# domus-silicea_-_N1_-_nRF24L01.net
KiCad netlist of a schematic drawn in EAGLE
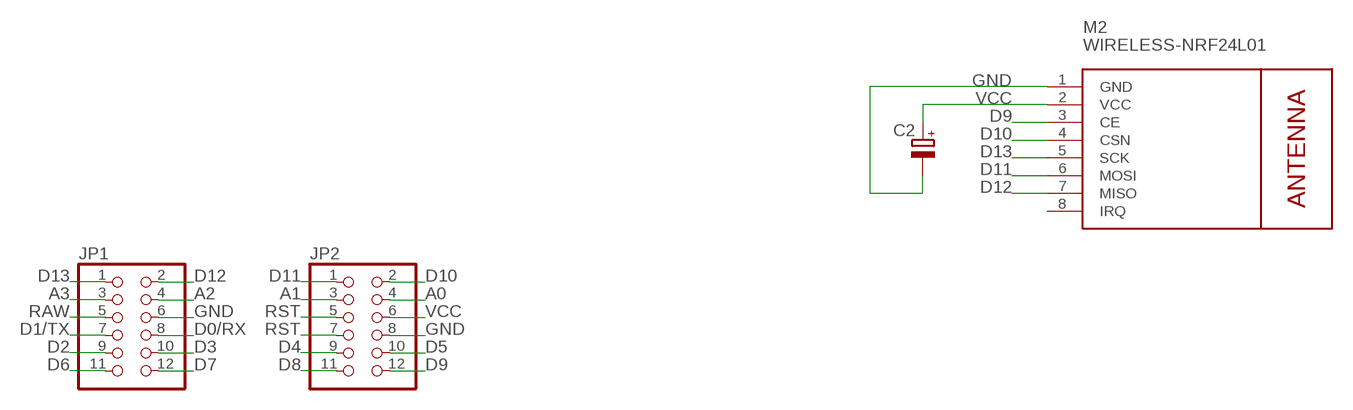
[diagram p0: schematic, sheet 1]

(export (version "E")
  (design (tool "Eeschema 10.0.6"))
  (components
    (comp (ref "C2")
      (value "CPOL-EUE2,5-6E")
      (footprint "eagle-import:E2,5-6E")
      (libsource (lib "eagle-import") (part "CPOL-EUE2,5-6E"))
    )
    (comp (ref "JP1")
      (value "PINHD-2X6")
      (footprint "eagle-import:2X06")
      (libsource (lib "eagle-import") (part "PINHD-2X6"))
    )
    (comp (ref "JP2")
      (value "PINHD-2X6")
      (footprint "eagle-import:2X06")
      (libsource (lib "eagle-import") (part "PINHD-2X6"))
    )
    (comp (ref "M2")
      (value "WIRELESS-NRF24L01")
      (footprint "eagle-import:WIRELESS-NRF24L01")
      (libsource (lib "eagle-import") (part "WIRELESS-NRF24L01"))
    )
  )
  (nets
    (net (code "1") (name "/A0") (class "Default")
      (node (ref "JP2") (pin "4") (pinfunction "4_4") (pintype "passive"))
    )
    (net (code "2") (name "/A1") (class "Default")
      (node (ref "JP2") (pin "3") (pinfunction "3_3") (pintype "passive"))
    )
    (net (code "3") (name "/A2") (class "Default")
      (node (ref "JP1") (pin "4") (pinfunction "4_4") (pintype "passive"))
    )
    (net (code "4") (name "/A3") (class "Default")
      (node (ref "JP1") (pin "3") (pinfunction "3_3") (pintype "passive"))
    )
    (net (code "5") (name "/D0{slash}RX") (class "Default")
      (node (ref "JP1") (pin "8") (pinfunction "8_8") (pintype "passive"))
    )
    (net (code "6") (name "/D1{slash}TX") (class "Default")
      (node (ref "JP1") (pin "7") (pinfunction "7_7") (pintype "passive"))
    )
    (net (code "7") (name "/D2") (class "Default")
      (node (ref "JP1") (pin "9") (pinfunction "9_9") (pintype "passive"))
    )
    (net (code "8") (name "/D3") (class "Default")
      (node (ref "JP1") (pin "10") (pinfunction "10_10") (pintype "passive"))
    )
    (net (code "9") (name "/D4") (class "Default")
      (node (ref "JP2") (pin "9") (pinfunction "9_9") (pintype "passive"))
    )
    (net (code "10") (name "/D5") (class "Default")
      (node (ref "JP2") (pin "10") (pinfunction "10_10") (pintype "passive"))
    )
    (net (code "11") (name "/D6") (class "Default")
      (node (ref "JP1") (pin "11") (pinfunction "11_11") (pintype "passive"))
    )
    (net (code "12") (name "/D7") (class "Default")
      (node (ref "JP1") (pin "12") (pinfunction "12_12") (pintype "passive"))
    )
    (net (code "13") (name "/D8") (class "Default")
      (node (ref "JP2") (pin "11") (pinfunction "11_11") (pintype "passive"))
    )
    (net (code "14") (name "/D9") (class "Default")
      (node (ref "JP2") (pin "12") (pinfunction "12_12") (pintype "passive"))
      (node (ref "M2") (pin "3") (pinfunction "CE_3") (pintype "bidirectional"))
    )
    (net (code "15") (name "/D10") (class "Default")
      (node (ref "JP2") (pin "2") (pinfunction "2_2") (pintype "passive"))
      (node (ref "M2") (pin "4") (pinfunction "CSN_4") (pintype "bidirectional"))
    )
    (net (code "16") (name "/D11") (class "Default")
      (node (ref "JP2") (pin "1") (pinfunction "1_1") (pintype "passive"))
      (node (ref "M2") (pin "6") (pinfunction "MOSI_6") (pintype "bidirectional"))
    )
    (net (code "17") (name "/D12") (class "Default")
      (node (ref "JP1") (pin "2") (pinfunction "2_2") (pintype "passive"))
      (node (ref "M2") (pin "7") (pinfunction "MISO_7") (pintype "bidirectional"))
    )
    (net (code "18") (name "/D13") (class "Default")
      (node (ref "JP1") (pin "1") (pinfunction "1_1") (pintype "passive"))
      (node (ref "M2") (pin "5") (pinfunction "SCK_5") (pintype "bidirectional"))
    )
    (net (code "19") (name "/GND") (class "Default")
      (node (ref "C2") (pin "-") (pinfunction "-_-") (pintype "passive"))
      (node (ref "JP1") (pin "6") (pinfunction "6_6") (pintype "passive"))
      (node (ref "JP2") (pin "8") (pinfunction "8_8") (pintype "passive"))
      (node (ref "M2") (pin "1") (pinfunction "GND_1") (pintype "power_in"))
    )
    (net (code "20") (name "/RAW") (class "Default")
      (node (ref "JP1") (pin "5") (pinfunction "5_5") (pintype "passive"))
    )
    (net (code "21") (name "/RST") (class "Default")
      (node (ref "JP2") (pin "5") (pinfunction "5_5") (pintype "passive"))
      (node (ref "JP2") (pin "7") (pinfunction "7_7") (pintype "passive"))
    )
    (net (code "22") (name "/VCC") (class "Default")
      (node (ref "C2") (pin "+") (pinfunction "+_+") (pintype "passive"))
      (node (ref "JP2") (pin "6") (pinfunction "6_6") (pintype "passive"))
      (node (ref "M2") (pin "2") (pinfunction "VCC_2") (pintype "power_in"))
    )
    (net (code "23") (name "unconnected-(M2-IRQ-Pad8)") (class "Default")
      (node (ref "M2") (pin "8") (pinfunction "IRQ_8") (pintype "bidirectional"))
    )
  )
)
